# octosonar-feather.net
KiCad netlist of a schematic drawn in EAGLE
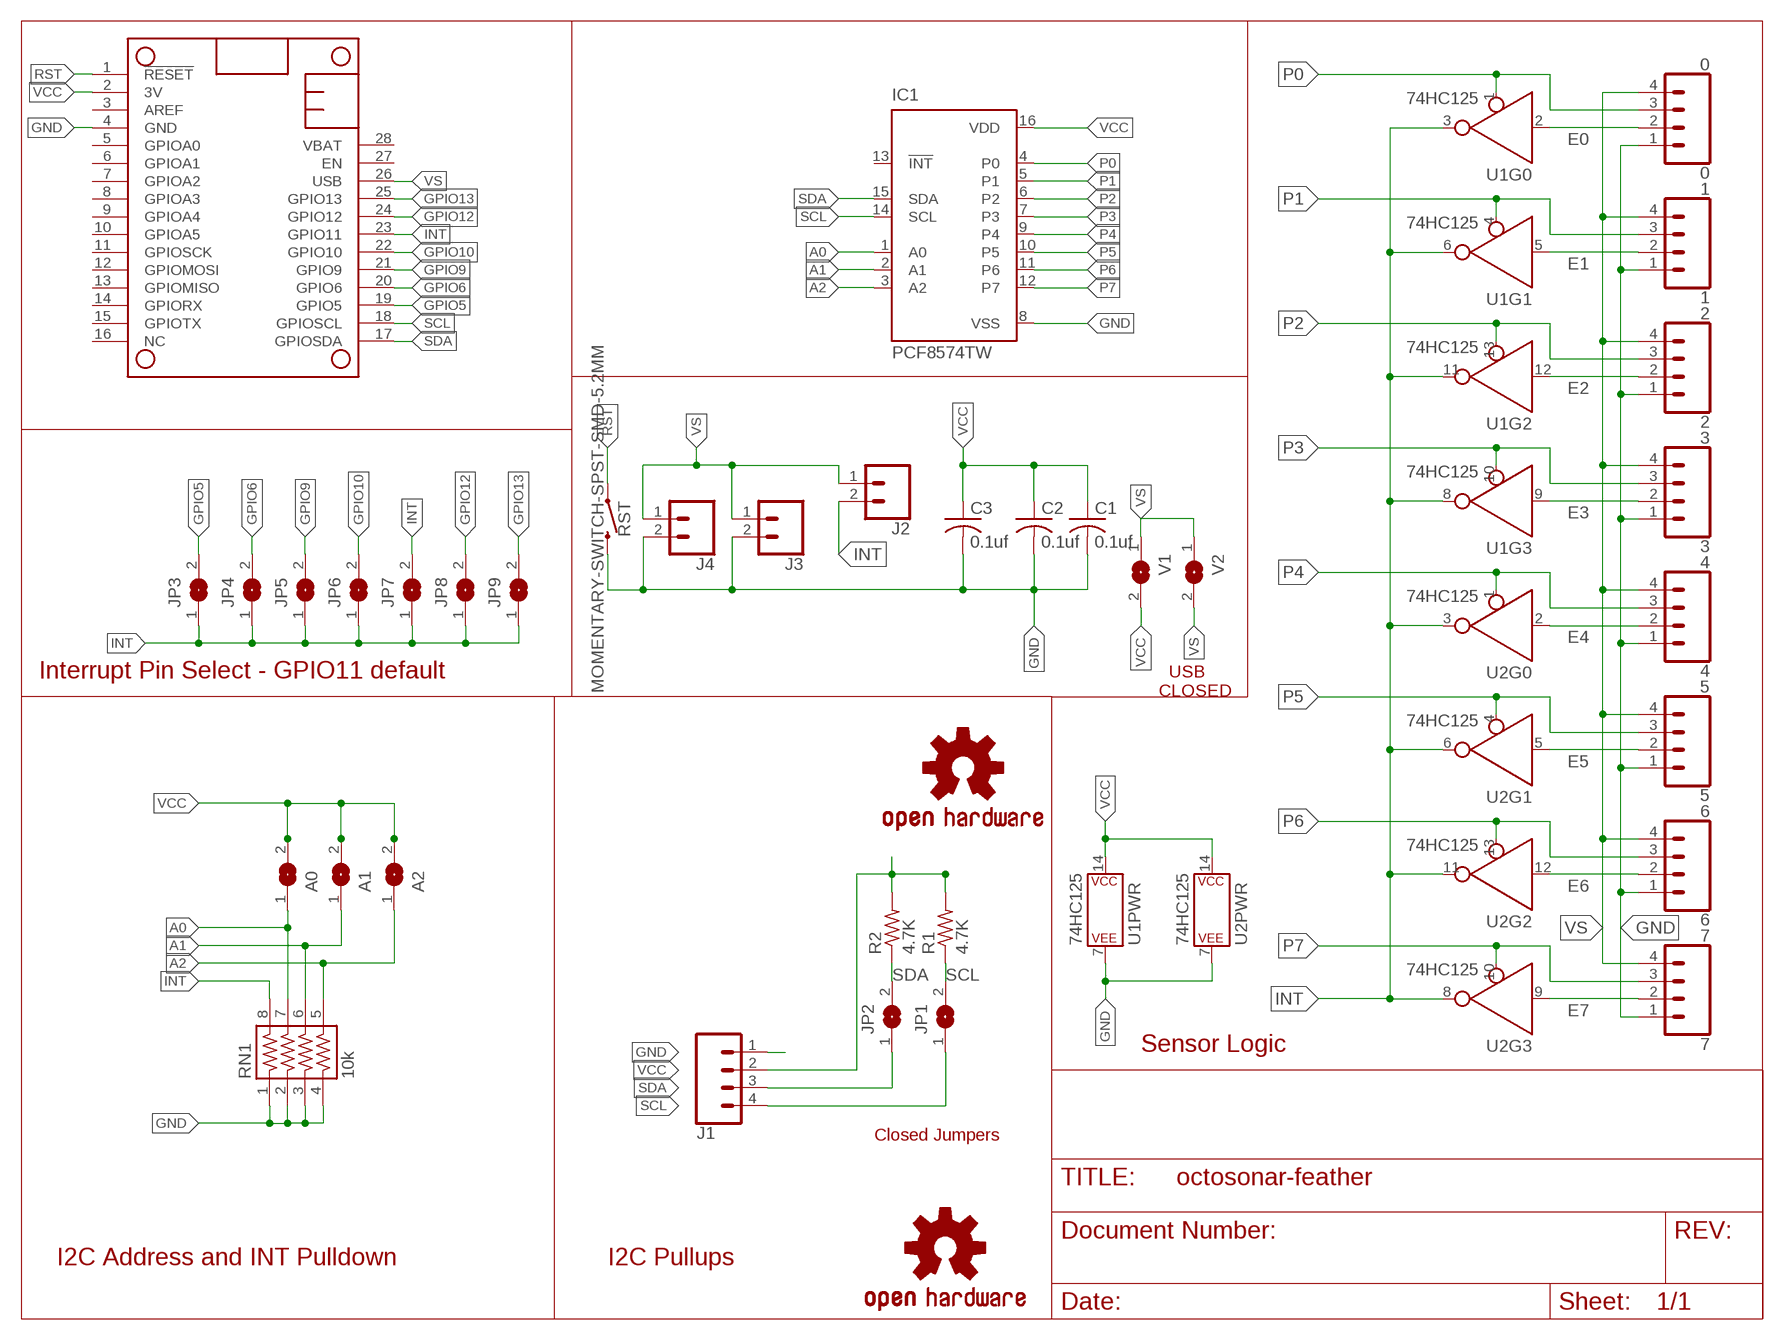
[diagram p0: schematic, sheet 1]

(export (version "E")
  (design (tool "Eeschema 10.0.6"))
  (components
    (comp (ref "0")
      (value "0")
      (footprint "eagle-import:1X04_NO_SILK")
      (libsource (lib "eagle-import") (part "CONN_041X04_NO_SILK"))
    )
    (comp (ref "1")
      (value "1")
      (footprint "eagle-import:1X04_NO_SILK")
      (libsource (lib "eagle-import") (part "CONN_041X04_NO_SILK"))
    )
    (comp (ref "2")
      (value "2")
      (footprint "eagle-import:1X04_NO_SILK")
      (libsource (lib "eagle-import") (part "CONN_041X04_NO_SILK"))
    )
    (comp (ref "3")
      (value "3")
      (footprint "eagle-import:1X04_NO_SILK")
      (libsource (lib "eagle-import") (part "CONN_041X04_NO_SILK"))
    )
    (comp (ref "4")
      (value "4")
      (footprint "eagle-import:1X04_NO_SILK")
      (libsource (lib "eagle-import") (part "CONN_041X04_NO_SILK"))
    )
    (comp (ref "5")
      (value "5")
      (footprint "eagle-import:1X04_NO_SILK")
      (libsource (lib "eagle-import") (part "CONN_041X04_NO_SILK"))
    )
    (comp (ref "6")
      (value "6")
      (footprint "eagle-import:1X04_NO_SILK")
      (libsource (lib "eagle-import") (part "CONN_041X04_NO_SILK"))
    )
    (comp (ref "7")
      (value "7")
      (footprint "eagle-import:1X04_NO_SILK")
      (libsource (lib "eagle-import") (part "CONN_041X04_NO_SILK"))
    )
    (comp (ref "A0")
      (value "SJSJ-NOCREAM")
      (footprint "eagle-import:SJ-NOCREAM")
      (libsource (lib "eagle-import") (part "SJSJ-NOCREAM"))
    )
    (comp (ref "A1")
      (value "SJSJ-NOCREAM")
      (footprint "eagle-import:SJ-NOCREAM")
      (libsource (lib "eagle-import") (part "SJSJ-NOCREAM"))
    )
    (comp (ref "A2")
      (value "SJSJ-NOCREAM")
      (footprint "eagle-import:SJ-NOCREAM")
      (libsource (lib "eagle-import") (part "SJSJ-NOCREAM"))
    )
    (comp (ref "C1")
      (value "0.1uf")
      (footprint "eagle-import:C0603")
      (libsource (lib "eagle-import") (part "C-USC0603"))
    )
    (comp (ref "C2")
      (value "0.1uf")
      (footprint "eagle-import:C0603")
      (libsource (lib "eagle-import") (part "C-USC0603"))
    )
    (comp (ref "C3")
      (value "0.1uf")
      (footprint "eagle-import:C0603")
      (libsource (lib "eagle-import") (part "C-USC0603"))
    )
    (comp (ref "IC1")
      (value "PCF8574TW")
      (footprint "eagle-import:SO16W")
      (fields (field (name "MPN") "PCF8574T/3,512"))
      (libsource (lib "eagle-import") (part "PCF8574TW"))
    )
    (comp (ref "J1")
      (value "CONN_041X04_NO_SILK")
      (footprint "eagle-import:1X04_NO_SILK")
      (libsource (lib "eagle-import") (part "CONN_041X04_NO_SILK"))
    )
    (comp (ref "J2")
      (value "CONN_021X02_NO_SILK")
      (footprint "eagle-import:1X02_NO_SILK")
      (libsource (lib "eagle-import") (part "CONN_021X02_NO_SILK"))
    )
    (comp (ref "J3")
      (value "CONN_021X02_NO_SILK")
      (footprint "eagle-import:1X02_NO_SILK")
      (libsource (lib "eagle-import") (part "CONN_021X02_NO_SILK"))
    )
    (comp (ref "J4")
      (value "CONN_021X02_NO_SILK")
      (footprint "eagle-import:1X02_NO_SILK")
      (libsource (lib "eagle-import") (part "CONN_021X02_NO_SILK"))
    )
    (comp (ref "JP1")
      (value "SJSJ-NOCREAM")
      (footprint "eagle-import:SJ-NOCREAM")
      (libsource (lib "eagle-import") (part "SJSJ-NOCREAM"))
    )
    (comp (ref "JP2")
      (value "SJSJ-NOCREAM")
      (footprint "eagle-import:SJ-NOCREAM")
      (libsource (lib "eagle-import") (part "SJSJ-NOCREAM"))
    )
    (comp (ref "JP3")
      (value "SJSJ-NOCREAM")
      (footprint "eagle-import:SJ-NOCREAM")
      (libsource (lib "eagle-import") (part "SJSJ-NOCREAM"))
    )
    (comp (ref "JP4")
      (value "SJSJ-NOCREAM")
      (footprint "eagle-import:SJ-NOCREAM")
      (libsource (lib "eagle-import") (part "SJSJ-NOCREAM"))
    )
    (comp (ref "JP5")
      (value "SJSJ-NOCREAM")
      (footprint "eagle-import:SJ-NOCREAM")
      (libsource (lib "eagle-import") (part "SJSJ-NOCREAM"))
    )
    (comp (ref "JP6")
      (value "SJSJ-NOCREAM")
      (footprint "eagle-import:SJ-NOCREAM")
      (libsource (lib "eagle-import") (part "SJSJ-NOCREAM"))
    )
    (comp (ref "JP7")
      (value "SJSJ-NOCREAM")
      (footprint "eagle-import:SJ-NOCREAM")
      (libsource (lib "eagle-import") (part "SJSJ-NOCREAM"))
    )
    (comp (ref "JP8")
      (value "SJSJ-NOCREAM")
      (footprint "eagle-import:SJ-NOCREAM")
      (libsource (lib "eagle-import") (part "SJSJ-NOCREAM"))
    )
    (comp (ref "JP9")
      (value "SJSJ-NOCREAM")
      (footprint "eagle-import:SJ-NOCREAM")
      (libsource (lib "eagle-import") (part "SJSJ-NOCREAM"))
    )
    (comp (ref "LOGO1")
      (value "OSHW-LOGOL-COPPER")
      (footprint "eagle-import:OSHW-LOGO-L_COPPER")
      (libsource (lib "eagle-import") (part "OSHW-LOGOL-COPPER"))
    )
    (comp (ref "LOGO2")
      (value "OSHW-LOGOL")
      (footprint "eagle-import:OSHW-LOGO-L")
      (libsource (lib "eagle-import") (part "OSHW-LOGOL"))
    )
    (comp (ref "MS1")
      (value "FEATHERWINGFEATHERWING_LONG")
      (footprint "eagle-import:FEATHERWING_LONG")
      (libsource (lib "eagle-import") (part "FEATHERWINGFEATHERWING_LONG"))
    )
    (comp (ref "R1")
      (value "4.7K")
      (footprint "eagle-import:R0603")
      (libsource (lib "eagle-import") (part "R-US_R0603"))
    )
    (comp (ref "R2")
      (value "4.7K")
      (footprint "eagle-import:R0603")
      (libsource (lib "eagle-import") (part "R-US_R0603"))
    )
    (comp (ref "RN1")
      (value "10k")
      (footprint "eagle-import:743-8")
      (libsource (lib "eagle-import") (part "743-8"))
    )
    (comp (ref "RST")
      (value "MOMENTARY-SWITCH-SPST-SMD-5.2MM")
      (footprint "eagle-import:TACTILE_SWITCH_SMD_5.2MM")
      (libsource (lib "eagle-import") (part "MOMENTARY-SWITCH-SPST-SMD-5.2MM"))
    )
    (comp (ref "U1")
      (value "74HC125")
      (footprint "eagle-import:SO14")
      (libsource (lib "eagle-import") (part "74125DGAC"))
    )
    (comp (ref "U2")
      (value "74HC125")
      (footprint "eagle-import:SO14")
      (libsource (lib "eagle-import") (part "74125DGAC"))
    )
    (comp (ref "V1")
      (value "SJSJ-NOCREAM")
      (footprint "eagle-import:SJ-NOCREAM")
      (libsource (lib "eagle-import") (part "SJSJ-NOCREAM"))
    )
    (comp (ref "V2")
      (value "SJSJ-NOCREAM")
      (footprint "eagle-import:SJ-NOCREAM")
      (libsource (lib "eagle-import") (part "SJSJ-NOCREAM"))
    )
  )
  (nets
    (net (code "1") (name "/E0") (class "Default")
      (node (ref "0") (pin "2") (pinfunction "2_2") (pintype "passive"))
      (node (ref "U1") (pin "2") (pinfunction "A_2") (pintype "bidirectional"))
    )
    (net (code "2") (name "/E1") (class "Default")
      (node (ref "1") (pin "2") (pinfunction "2_2") (pintype "passive"))
      (node (ref "U1") (pin "5") (pinfunction "A_5") (pintype "bidirectional"))
    )
    (net (code "3") (name "/E2") (class "Default")
      (node (ref "2") (pin "2") (pinfunction "2_2") (pintype "passive"))
      (node (ref "U1") (pin "12") (pinfunction "A_12") (pintype "bidirectional"))
    )
    (net (code "4") (name "/E3") (class "Default")
      (node (ref "3") (pin "2") (pinfunction "2_2") (pintype "passive"))
      (node (ref "U1") (pin "9") (pinfunction "A_9") (pintype "bidirectional"))
    )
    (net (code "5") (name "/E4") (class "Default")
      (node (ref "4") (pin "2") (pinfunction "2_2") (pintype "passive"))
      (node (ref "U2") (pin "2") (pinfunction "A_2") (pintype "bidirectional"))
    )
    (net (code "6") (name "/E5") (class "Default")
      (node (ref "5") (pin "2") (pinfunction "2_2") (pintype "passive"))
      (node (ref "U2") (pin "5") (pinfunction "A_5") (pintype "bidirectional"))
    )
    (net (code "7") (name "/E6") (class "Default")
      (node (ref "6") (pin "2") (pinfunction "2_2") (pintype "passive"))
      (node (ref "U2") (pin "12") (pinfunction "A_12") (pintype "bidirectional"))
    )
    (net (code "8") (name "/E7") (class "Default")
      (node (ref "7") (pin "2") (pinfunction "2_2") (pintype "passive"))
      (node (ref "U2") (pin "9") (pinfunction "A_9") (pintype "bidirectional"))
    )
    (net (code "9") (name "/VBAT") (class "Default")
      (node (ref "MS1") (pin "28") (pinfunction "VBAT_28") (pintype "power_in"))
    )
    (net (code "10") (name "A0") (class "Default")
      (node (ref "A0") (pin "1") (pinfunction "1_1") (pintype "passive"))
      (node (ref "IC1") (pin "1") (pinfunction "A0_1") (pintype "input"))
      (node (ref "RN1") (pin "7") (pinfunction "7_7") (pintype "passive"))
    )
    (net (code "11") (name "A1") (class "Default")
      (node (ref "A1") (pin "1") (pinfunction "1_1") (pintype "passive"))
      (node (ref "IC1") (pin "2") (pinfunction "A1_2") (pintype "input"))
      (node (ref "RN1") (pin "6") (pinfunction "6_6") (pintype "passive"))
    )
    (net (code "12") (name "A2") (class "Default")
      (node (ref "A2") (pin "1") (pinfunction "1_1") (pintype "passive"))
      (node (ref "IC1") (pin "3") (pinfunction "A2_3") (pintype "input"))
      (node (ref "RN1") (pin "5") (pinfunction "5_5") (pintype "passive"))
    )
    (net (code "13") (name "GND") (class "Default")
      (node (ref "0") (pin "1") (pinfunction "1_1") (pintype "passive"))
      (node (ref "1") (pin "1") (pinfunction "1_1") (pintype "passive"))
      (node (ref "2") (pin "1") (pinfunction "1_1") (pintype "passive"))
      (node (ref "3") (pin "1") (pinfunction "1_1") (pintype "passive"))
      (node (ref "4") (pin "1") (pinfunction "1_1") (pintype "passive"))
      (node (ref "5") (pin "1") (pinfunction "1_1") (pintype "passive"))
      (node (ref "6") (pin "1") (pinfunction "1_1") (pintype "passive"))
      (node (ref "7") (pin "1") (pinfunction "1_1") (pintype "passive"))
      (node (ref "C1") (pin "2") (pinfunction "2_2") (pintype "passive"))
      (node (ref "C2") (pin "2") (pinfunction "2_2") (pintype "passive"))
      (node (ref "C3") (pin "2") (pinfunction "2_2") (pintype "passive"))
      (node (ref "IC1") (pin "8") (pinfunction "VSS_8") (pintype "power_in"))
      (node (ref "J1") (pin "1") (pinfunction "1_1") (pintype "passive"))
      (node (ref "J3") (pin "2") (pinfunction "2_2") (pintype "passive"))
      (node (ref "J4") (pin "2") (pinfunction "2_2") (pintype "passive"))
      (node (ref "MS1") (pin "4") (pinfunction "GND_4") (pintype "power_in"))
      (node (ref "RN1") (pin "1") (pinfunction "1_1") (pintype "passive"))
      (node (ref "RN1") (pin "2") (pinfunction "2_2") (pintype "passive"))
      (node (ref "RN1") (pin "3") (pinfunction "3_3") (pintype "passive"))
      (node (ref "RN1") (pin "4") (pinfunction "4_4") (pintype "passive"))
      (node (ref "RST") (pin "3") (pinfunction "2_3") (pintype "passive"))
      (node (ref "U1") (pin "7") (pinfunction "P$V-_7") (pintype "bidirectional"))
      (node (ref "U2") (pin "7") (pinfunction "P$V-_7") (pintype "bidirectional"))
    )
    (net (code "14") (name "GPIO5") (class "Default")
      (node (ref "JP3") (pin "2") (pinfunction "2_2") (pintype "passive"))
      (node (ref "MS1") (pin "19") (pinfunction "GPIO5_19") (pintype "bidirectional"))
    )
    (net (code "15") (name "GPIO6") (class "Default")
      (node (ref "JP4") (pin "2") (pinfunction "2_2") (pintype "passive"))
      (node (ref "MS1") (pin "20") (pinfunction "GPIO6_20") (pintype "bidirectional"))
    )
    (net (code "16") (name "GPIO9") (class "Default")
      (node (ref "JP5") (pin "2") (pinfunction "2_2") (pintype "passive"))
      (node (ref "MS1") (pin "21") (pinfunction "GPIO9_21") (pintype "bidirectional"))
    )
    (net (code "17") (name "GPIO10") (class "Default")
      (node (ref "JP6") (pin "2") (pinfunction "2_2") (pintype "passive"))
      (node (ref "MS1") (pin "22") (pinfunction "GPIO10_22") (pintype "bidirectional"))
    )
    (net (code "18") (name "GPIO12") (class "Default")
      (node (ref "JP8") (pin "2") (pinfunction "2_2") (pintype "passive"))
      (node (ref "MS1") (pin "24") (pinfunction "GPIO12_24") (pintype "bidirectional"))
    )
    (net (code "19") (name "GPIO13") (class "Default")
      (node (ref "JP9") (pin "2") (pinfunction "2_2") (pintype "passive"))
      (node (ref "MS1") (pin "25") (pinfunction "GPIO13_25") (pintype "bidirectional"))
    )
    (net (code "20") (name "INT") (class "Default")
      (node (ref "J2") (pin "2") (pinfunction "2_2") (pintype "passive"))
      (node (ref "JP3") (pin "1") (pinfunction "1_1") (pintype "passive"))
      (node (ref "JP4") (pin "1") (pinfunction "1_1") (pintype "passive"))
      (node (ref "JP5") (pin "1") (pinfunction "1_1") (pintype "passive"))
      (node (ref "JP6") (pin "1") (pinfunction "1_1") (pintype "passive"))
      (node (ref "JP7") (pin "1") (pinfunction "1_1") (pintype "passive"))
      (node (ref "JP7") (pin "2") (pinfunction "2_2") (pintype "passive"))
      (node (ref "JP8") (pin "1") (pinfunction "1_1") (pintype "passive"))
      (node (ref "JP9") (pin "1") (pinfunction "1_1") (pintype "passive"))
      (node (ref "MS1") (pin "23") (pinfunction "GPIO11_23") (pintype "bidirectional"))
      (node (ref "RN1") (pin "8") (pinfunction "8_8") (pintype "passive"))
      (node (ref "U1") (pin "11") (pinfunction "Y_11") (pintype "bidirectional"))
      (node (ref "U1") (pin "3") (pinfunction "Y_3") (pintype "bidirectional"))
      (node (ref "U1") (pin "6") (pinfunction "Y_6") (pintype "bidirectional"))
      (node (ref "U1") (pin "8") (pinfunction "Y_8") (pintype "bidirectional"))
      (node (ref "U2") (pin "11") (pinfunction "Y_11") (pintype "bidirectional"))
      (node (ref "U2") (pin "3") (pinfunction "Y_3") (pintype "bidirectional"))
      (node (ref "U2") (pin "6") (pinfunction "Y_6") (pintype "bidirectional"))
      (node (ref "U2") (pin "8") (pinfunction "Y_8") (pintype "bidirectional"))
    )
    (net (code "21") (name "P0") (class "Default")
      (node (ref "0") (pin "3") (pinfunction "3_3") (pintype "passive"))
      (node (ref "IC1") (pin "4") (pinfunction "P0_4") (pintype "bidirectional"))
      (node (ref "U1") (pin "1") (pinfunction "~{EN}_1") (pintype "bidirectional"))
    )
    (net (code "22") (name "P1") (class "Default")
      (node (ref "1") (pin "3") (pinfunction "3_3") (pintype "passive"))
      (node (ref "IC1") (pin "5") (pinfunction "P1_5") (pintype "bidirectional"))
      (node (ref "U1") (pin "4") (pinfunction "~{EN}_4") (pintype "bidirectional"))
    )
    (net (code "23") (name "P2") (class "Default")
      (node (ref "2") (pin "3") (pinfunction "3_3") (pintype "passive"))
      (node (ref "IC1") (pin "6") (pinfunction "P2_6") (pintype "bidirectional"))
      (node (ref "U1") (pin "13") (pinfunction "~{EN}_13") (pintype "bidirectional"))
    )
    (net (code "24") (name "P3") (class "Default")
      (node (ref "3") (pin "3") (pinfunction "3_3") (pintype "passive"))
      (node (ref "IC1") (pin "7") (pinfunction "P3_7") (pintype "bidirectional"))
      (node (ref "U1") (pin "10") (pinfunction "~{EN}_10") (pintype "bidirectional"))
    )
    (net (code "25") (name "P4") (class "Default")
      (node (ref "4") (pin "3") (pinfunction "3_3") (pintype "passive"))
      (node (ref "IC1") (pin "9") (pinfunction "P4_9") (pintype "bidirectional"))
      (node (ref "U2") (pin "1") (pinfunction "~{EN}_1") (pintype "bidirectional"))
    )
    (net (code "26") (name "P5") (class "Default")
      (node (ref "5") (pin "3") (pinfunction "3_3") (pintype "passive"))
      (node (ref "IC1") (pin "10") (pinfunction "P5_10") (pintype "bidirectional"))
      (node (ref "U2") (pin "4") (pinfunction "~{EN}_4") (pintype "bidirectional"))
    )
    (net (code "27") (name "P6") (class "Default")
      (node (ref "6") (pin "3") (pinfunction "3_3") (pintype "passive"))
      (node (ref "IC1") (pin "11") (pinfunction "P6_11") (pintype "bidirectional"))
      (node (ref "U2") (pin "13") (pinfunction "~{EN}_13") (pintype "bidirectional"))
    )
    (net (code "28") (name "P7") (class "Default")
      (node (ref "7") (pin "3") (pinfunction "3_3") (pintype "passive"))
      (node (ref "IC1") (pin "12") (pinfunction "P7_12") (pintype "bidirectional"))
      (node (ref "U2") (pin "10") (pinfunction "~{EN}_10") (pintype "bidirectional"))
    )
    (net (code "29") (name "RST") (class "Default")
      (node (ref "MS1") (pin "1") (pinfunction "~{RESET}_1") (pintype "input"))
      (node (ref "RST") (pin "1") (pinfunction "1_1") (pintype "passive"))
    )
    (net (code "30") (name "SCL") (class "Default")
      (node (ref "IC1") (pin "14") (pinfunction "SCL_14") (pintype "input"))
      (node (ref "J1") (pin "4") (pinfunction "4_4") (pintype "passive"))
      (node (ref "JP1") (pin "1") (pinfunction "1_1") (pintype "passive"))
      (node (ref "JP1") (pin "2") (pinfunction "2_2") (pintype "passive"))
      (node (ref "MS1") (pin "18") (pinfunction "GPIOSCL_18") (pintype "bidirectional"))
      (node (ref "R1") (pin "1") (pinfunction "1_1") (pintype "passive"))
    )
    (net (code "31") (name "SDA") (class "Default")
      (node (ref "IC1") (pin "15") (pinfunction "SDA_15") (pintype "bidirectional"))
      (node (ref "J1") (pin "3") (pinfunction "3_3") (pintype "passive"))
      (node (ref "JP2") (pin "1") (pinfunction "1_1") (pintype "passive"))
      (node (ref "JP2") (pin "2") (pinfunction "2_2") (pintype "passive"))
      (node (ref "MS1") (pin "17") (pinfunction "GPIOSDA_17") (pintype "bidirectional"))
      (node (ref "R2") (pin "1") (pinfunction "1_1") (pintype "passive"))
    )
    (net (code "32") (name "VCC") (class "Default")
      (node (ref "A0") (pin "2") (pinfunction "2_2") (pintype "passive"))
      (node (ref "A1") (pin "2") (pinfunction "2_2") (pintype "passive"))
      (node (ref "A2") (pin "2") (pinfunction "2_2") (pintype "passive"))
      (node (ref "C1") (pin "1") (pinfunction "1_1") (pintype "passive"))
      (node (ref "C2") (pin "1") (pinfunction "1_1") (pintype "passive"))
      (node (ref "C3") (pin "1") (pinfunction "1_1") (pintype "passive"))
      (node (ref "IC1") (pin "16") (pinfunction "VDD_16") (pintype "power_in"))
      (node (ref "J1") (pin "2") (pinfunction "2_2") (pintype "passive"))
      (node (ref "MS1") (pin "2") (pinfunction "3V_2") (pintype "power_in"))
      (node (ref "R1") (pin "2") (pinfunction "2_2") (pintype "passive"))
      (node (ref "R2") (pin "2") (pinfunction "2_2") (pintype "passive"))
      (node (ref "U1") (pin "14") (pinfunction "P$V+_14") (pintype "bidirectional"))
      (node (ref "U2") (pin "14") (pinfunction "P$V+_14") (pintype "bidirectional"))
      (node (ref "V1") (pin "2") (pinfunction "2_2") (pintype "passive"))
    )
    (net (code "33") (name "VS") (class "Default")
      (node (ref "0") (pin "4") (pinfunction "4_4") (pintype "passive"))
      (node (ref "1") (pin "4") (pinfunction "4_4") (pintype "passive"))
      (node (ref "2") (pin "4") (pinfunction "4_4") (pintype "passive"))
      (node (ref "3") (pin "4") (pinfunction "4_4") (pintype "passive"))
      (node (ref "4") (pin "4") (pinfunction "4_4") (pintype "passive"))
      (node (ref "5") (pin "4") (pinfunction "4_4") (pintype "passive"))
      (node (ref "6") (pin "4") (pinfunction "4_4") (pintype "passive"))
      (node (ref "7") (pin "4") (pinfunction "4_4") (pintype "passive"))
      (node (ref "J2") (pin "1") (pinfunction "1_1") (pintype "passive"))
      (node (ref "J3") (pin "1") (pinfunction "1_1") (pintype "passive"))
      (node (ref "J4") (pin "1") (pinfunction "1_1") (pintype "passive"))
      (node (ref "MS1") (pin "26") (pinfunction "USB_26") (pintype "power_in"))
      (node (ref "V1") (pin "1") (pinfunction "1_1") (pintype "passive"))
      (node (ref "V2") (pin "1") (pinfunction "1_1") (pintype "passive"))
      (node (ref "V2") (pin "2") (pinfunction "2_2") (pintype "passive"))
    )
    (net (code "34") (name "unconnected-(IC1-~{INT}-Pad13)") (class "Default")
      (node (ref "IC1") (pin "13") (pinfunction "~{INT}_13") (pintype "output"))
    )
    (net (code "35") (name "unconnected-(MS1-AREF-Pad3)") (class "Default")
      (node (ref "MS1") (pin "3") (pinfunction "AREF_3") (pintype "passive"))
    )
    (net (code "36") (name "unconnected-(MS1-EN-Pad27)") (class "Default")
      (node (ref "MS1") (pin "27") (pinfunction "EN_27") (pintype "passive"))
    )
    (net (code "37") (name "unconnected-(MS1-GPIOA0-Pad5)") (class "Default")
      (node (ref "MS1") (pin "5") (pinfunction "GPIOA0_5") (pintype "bidirectional"))
    )
    (net (code "38") (name "unconnected-(MS1-GPIOA1-Pad6)") (class "Default")
      (node (ref "MS1") (pin "6") (pinfunction "GPIOA1_6") (pintype "bidirectional"))
    )
    (net (code "39") (name "unconnected-(MS1-GPIOA2-Pad7)") (class "Default")
      (node (ref "MS1") (pin "7") (pinfunction "GPIOA2_7") (pintype "bidirectional"))
    )
    (net (code "40") (name "unconnected-(MS1-GPIOA3-Pad8)") (class "Default")
      (node (ref "MS1") (pin "8") (pinfunction "GPIOA3_8") (pintype "bidirectional"))
    )
    (net (code "41") (name "unconnected-(MS1-GPIOA4-Pad9)") (class "Default")
      (node (ref "MS1") (pin "9") (pinfunction "GPIOA4_9") (pintype "bidirectional"))
    )
    (net (code "42") (name "unconnected-(MS1-GPIOA5-Pad10)") (class "Default")
      (node (ref "MS1") (pin "10") (pinfunction "GPIOA5_10") (pintype "bidirectional"))
    )
    (net (code "43") (name "unconnected-(MS1-GPIOMISO-Pad13)") (class "Default")
      (node (ref "MS1") (pin "13") (pinfunction "GPIOMISO_13") (pintype "bidirectional"))
    )
    (net (code "44") (name "unconnected-(MS1-GPIOMOSI-Pad12)") (class "Default")
      (node (ref "MS1") (pin "12") (pinfunction "GPIOMOSI_12") (pintype "bidirectional"))
    )
    (net (code "45") (name "unconnected-(MS1-GPIORX-Pad14)") (class "Default")
      (node (ref "MS1") (pin "14") (pinfunction "GPIORX_14") (pintype "bidirectional"))
    )
    (net (code "46") (name "unconnected-(MS1-GPIOSCK-Pad11)") (class "Default")
      (node (ref "MS1") (pin "11") (pinfunction "GPIOSCK_11") (pintype "bidirectional"))
    )
    (net (code "47") (name "unconnected-(MS1-GPIOTX-Pad15)") (class "Default")
      (node (ref "MS1") (pin "15") (pinfunction "GPIOTX_15") (pintype "bidirectional"))
    )
    (net (code "48") (name "unconnected-(MS1-NC-Pad16)") (class "Default")
      (node (ref "MS1") (pin "16") (pinfunction "NC_16") (pintype "passive"))
    )
  )
)
